# Elektronisch_schema_PCB.net
KiCad netlist of a schematic drawn in EasyEDA
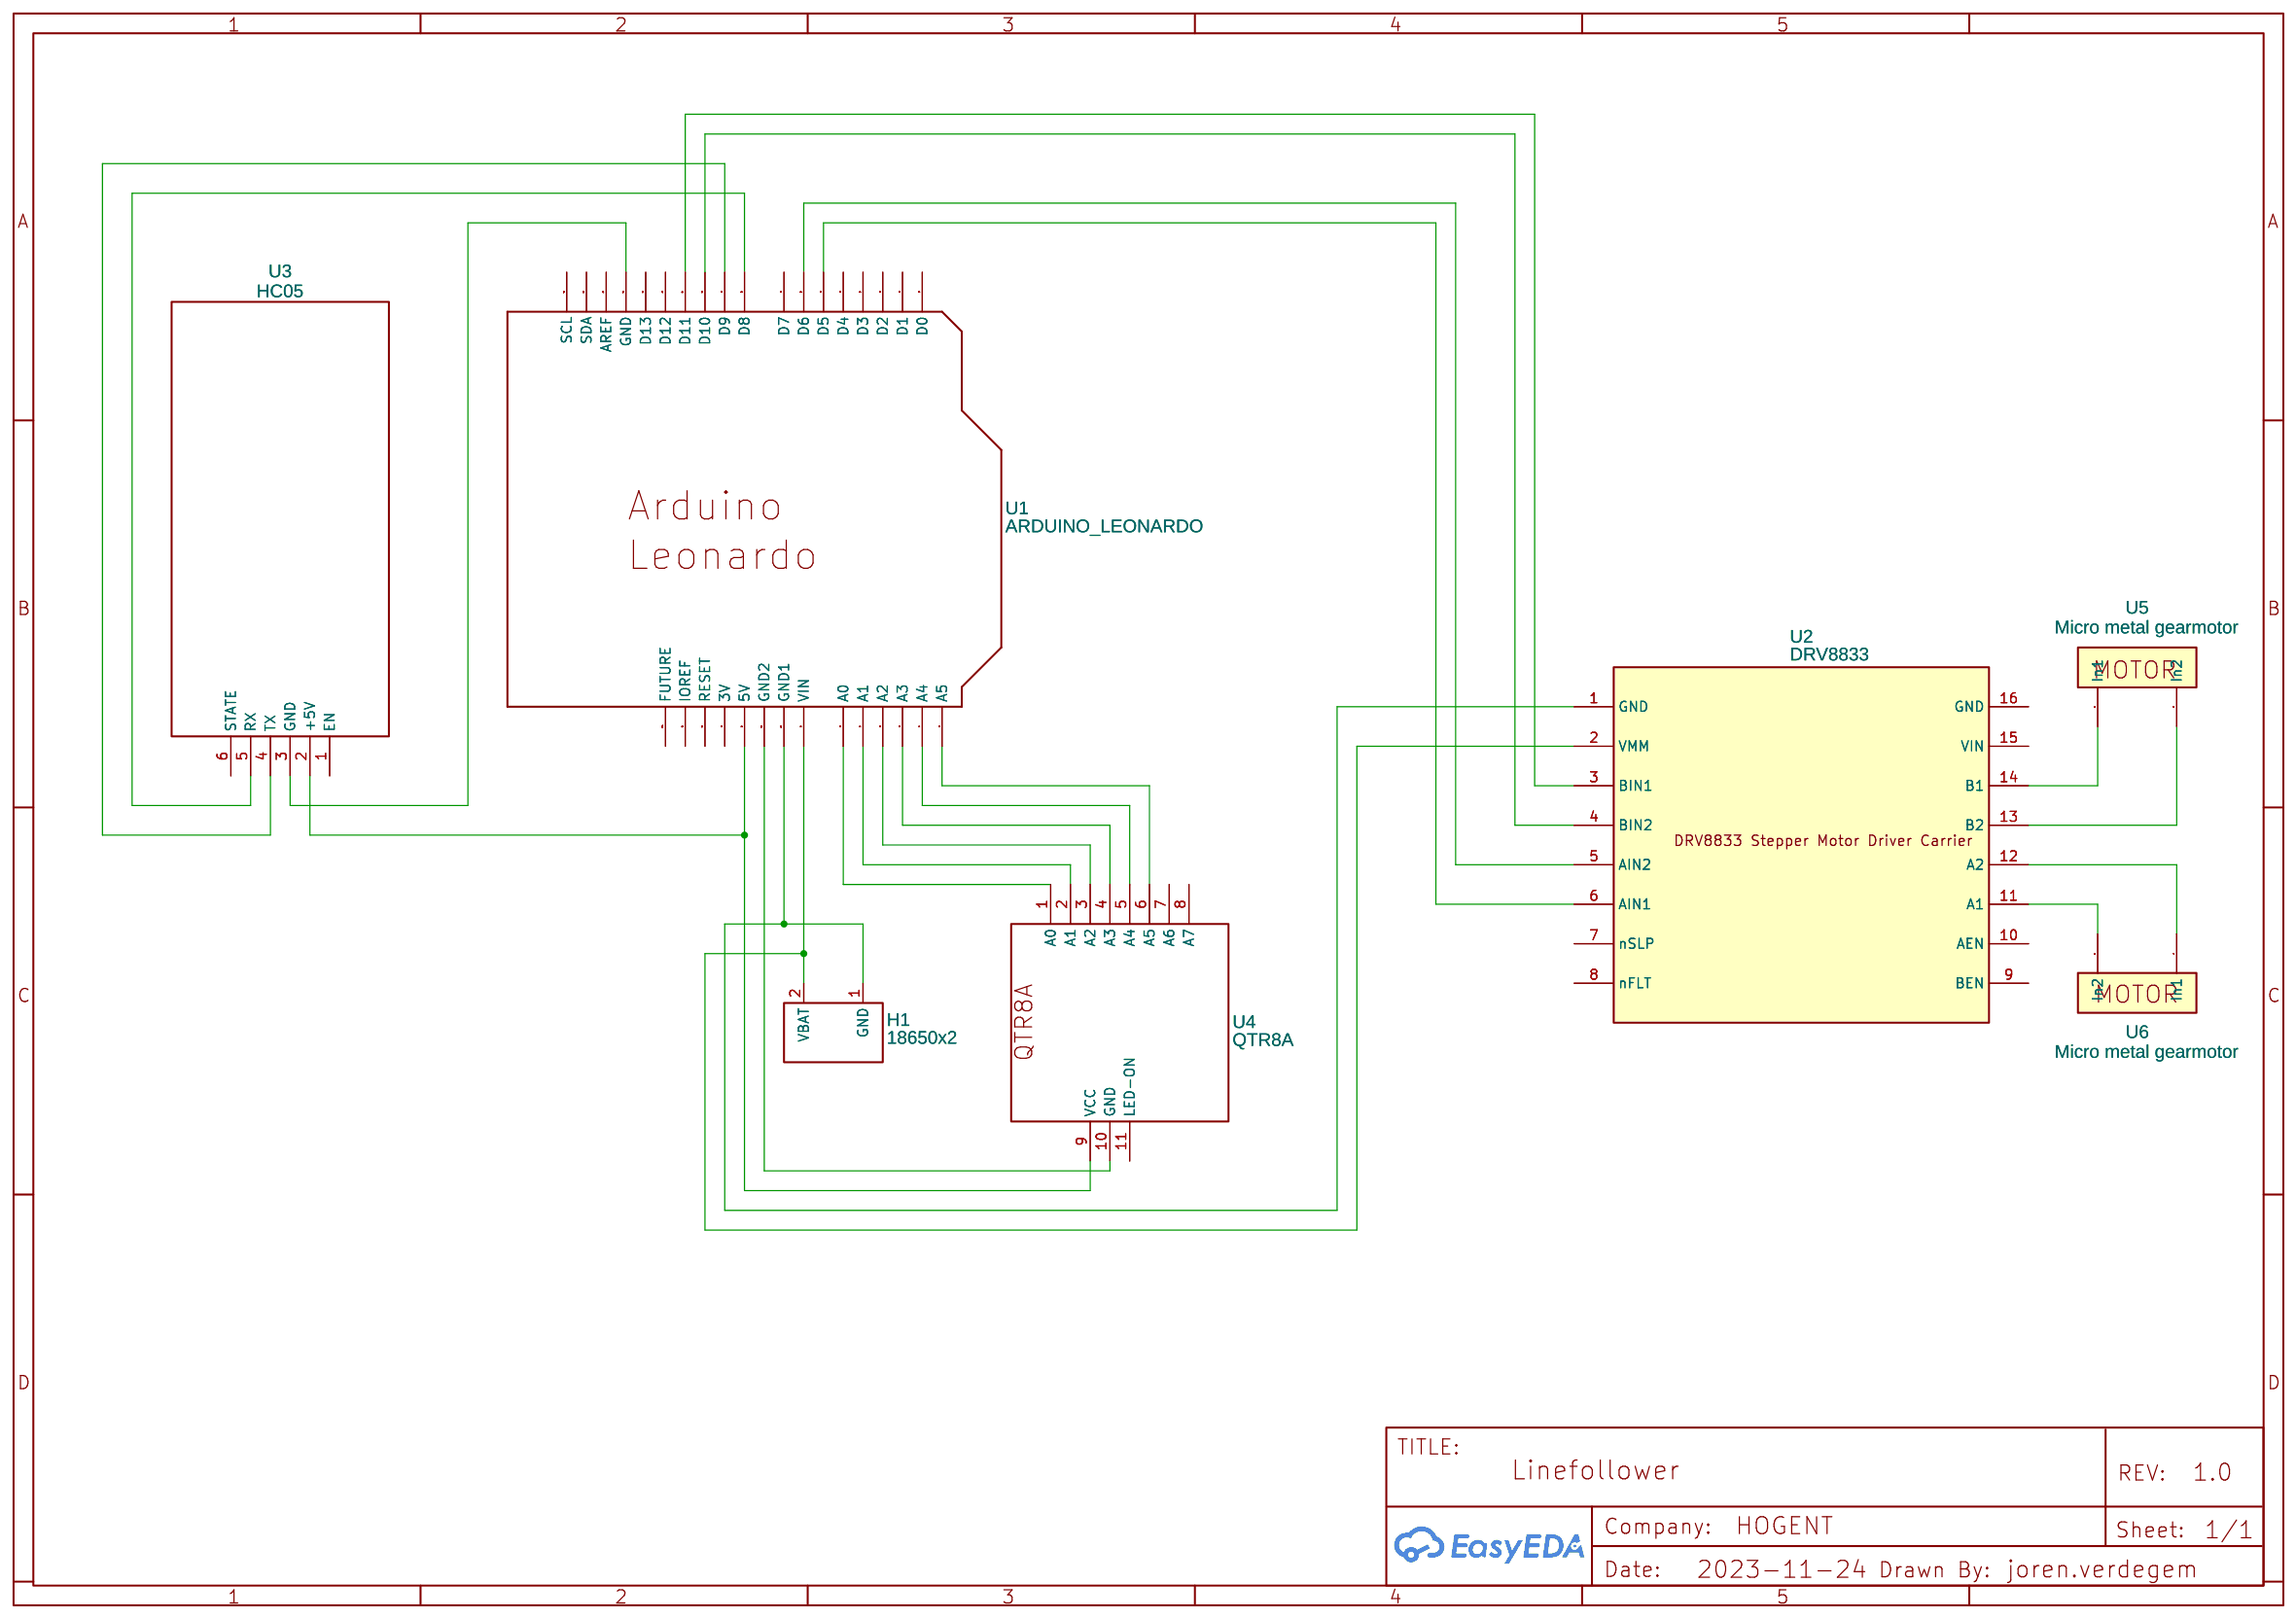
[diagram p0: schematic sheet]

(export (version "E")
  (design (tool "Eeschema 10.0.6"))
  (components
    (comp (ref "H1") (value "18650x2") (libsource (lib "") (part "18650x2")))
    (comp (ref "U1") (value "ARDUINO_LEONARDO") (libsource (lib "") (part "ARDUINO_LEONARDO")))
    (comp (ref "U2") (value "DRV8833") (libsource (lib "") (part "DRV8833 Stepper Motor Driver Carrier")))
    (comp (ref "U3") (value "HC05") (libsource (lib "") (part "HC05")))
    (comp (ref "U4")
      (value "QTR8A")
      (fields (field (name "Manufacturer") "POLOLU"))
      (libsource (lib "") (part "SCHLIB_QTR8A_2023-02-18"))
    )
    (comp (ref "U5")
      (value "Micro metal gearmotor")
      (fields (field (name "Manufacturer Part") "3062") (field (name "Manufacturer") "Pololu"))
      (libsource (lib "") (part "Micro metal gearmotor"))
    )
    (comp (ref "U6")
      (value "Micro metal gearmotor")
      (fields (field (name "Manufacturer Part") "3062") (field (name "Manufacturer") "Pololu"))
      (libsource (lib "") (part "Micro metal gearmotor_1"))
    )
  )
  (nets
    (net (code "1") (name "Net-(H1-GND)") (class "Default")
      (node (ref "H1") (pin "1") (pinfunction "GND_1") (pintype "unspecified"))
      (node (ref "U1") (pin "GND$3") (pinfunction "GND1_GND$3") (pintype "passive"))
      (node (ref "U2") (pin "1") (pinfunction "GND_1") (pintype "unspecified"))
    )
    (net (code "2") (name "Net-(H1-VBAT)") (class "Default")
      (node (ref "H1") (pin "2") (pinfunction "VBAT_2") (pintype "unspecified"))
      (node (ref "U1") (pin "VIN") (pinfunction "VIN_VIN") (pintype "passive"))
      (node (ref "U2") (pin "2") (pinfunction "VMM_2") (pintype "unspecified"))
    )
    (net (code "3") (name "Net-(U1-GND2)") (class "Default")
      (node (ref "U1") (pin "GND$2") (pinfunction "GND2_GND$2") (pintype "passive"))
      (node (ref "U4") (pin "10") (pinfunction "GND_10") (pintype "unspecified"))
    )
    (net (code "4") (name "Net-(U2-A1)") (class "Default")
      (node (ref "U2") (pin "11") (pinfunction "A1_11") (pintype "unspecified"))
      (node (ref "U6") (pin "2") (pinfunction "In2_2") (pintype "unspecified"))
    )
    (net (code "5") (name "Net-(U2-A2)") (class "Default")
      (node (ref "U2") (pin "12") (pinfunction "A2_12") (pintype "unspecified"))
      (node (ref "U6") (pin "1") (pinfunction "In1_1") (pintype "unspecified"))
    )
    (net (code "6") (name "Net-(U2-AIN1)") (class "Default")
      (node (ref "U1") (pin "D5") (pinfunction "D5_D5") (pintype "unspecified"))
      (node (ref "U2") (pin "6") (pinfunction "AIN1_6") (pintype "unspecified"))
    )
    (net (code "7") (name "Net-(U2-AIN2)") (class "Default")
      (node (ref "U1") (pin "D6") (pinfunction "D6_D6") (pintype "unspecified"))
      (node (ref "U2") (pin "5") (pinfunction "AIN2_5") (pintype "unspecified"))
    )
    (net (code "8") (name "Net-(U2-B1)") (class "Default")
      (node (ref "U2") (pin "14") (pinfunction "B1_14") (pintype "unspecified"))
      (node (ref "U5") (pin "1") (pinfunction "In1_1") (pintype "unspecified"))
    )
    (net (code "9") (name "Net-(U2-B2)") (class "Default")
      (node (ref "U2") (pin "13") (pinfunction "B2_13") (pintype "unspecified"))
      (node (ref "U5") (pin "2") (pinfunction "In2_2") (pintype "unspecified"))
    )
    (net (code "10") (name "Net-(U2-BIN1)") (class "Default")
      (node (ref "U1") (pin "D11") (pinfunction "D11_D11") (pintype "unspecified"))
      (node (ref "U2") (pin "3") (pinfunction "BIN1_3") (pintype "unspecified"))
    )
    (net (code "11") (name "Net-(U2-BIN2)") (class "Default")
      (node (ref "U1") (pin "D10") (pinfunction "D10_D10") (pintype "unspecified"))
      (node (ref "U2") (pin "4") (pinfunction "BIN2_4") (pintype "unspecified"))
    )
    (net (code "12") (name "Net-(U3-+5V)") (class "Default")
      (node (ref "U1") (pin "5V") (pinfunction "5V_5V") (pintype "passive"))
      (node (ref "U3") (pin "2") (pinfunction "+5V_2") (pintype "unspecified"))
      (node (ref "U4") (pin "9") (pinfunction "VCC_9") (pintype "unspecified"))
    )
    (net (code "13") (name "Net-(U3-GND)") (class "Default")
      (node (ref "U1") (pin "GND") (pinfunction "GND_GND") (pintype "passive"))
      (node (ref "U3") (pin "3") (pinfunction "GND_3") (pintype "unspecified"))
    )
    (net (code "14") (name "Net-(U3-RX)") (class "Default")
      (node (ref "U1") (pin "D8") (pinfunction "D8_D8") (pintype "unspecified"))
      (node (ref "U3") (pin "5") (pinfunction "RX_5") (pintype "unspecified"))
    )
    (net (code "15") (name "Net-(U3-TX)") (class "Default")
      (node (ref "U1") (pin "D9") (pinfunction "D9_D9") (pintype "unspecified"))
      (node (ref "U3") (pin "4") (pinfunction "TX_4") (pintype "unspecified"))
    )
    (net (code "16") (name "Net-(U4-A0)") (class "Default")
      (node (ref "U1") (pin "A0") (pinfunction "A0_A0") (pintype "unspecified"))
      (node (ref "U4") (pin "1") (pinfunction "A0_1") (pintype "unspecified"))
    )
    (net (code "17") (name "Net-(U4-A1)") (class "Default")
      (node (ref "U1") (pin "A1") (pinfunction "A1_A1") (pintype "unspecified"))
      (node (ref "U4") (pin "2") (pinfunction "A1_2") (pintype "unspecified"))
    )
    (net (code "18") (name "Net-(U4-A2)") (class "Default")
      (node (ref "U1") (pin "A2") (pinfunction "A2_A2") (pintype "unspecified"))
      (node (ref "U4") (pin "3") (pinfunction "A2_3") (pintype "unspecified"))
    )
    (net (code "19") (name "Net-(U4-A3)") (class "Default")
      (node (ref "U1") (pin "A3") (pinfunction "A3_A3") (pintype "unspecified"))
      (node (ref "U4") (pin "4") (pinfunction "A3_4") (pintype "unspecified"))
    )
    (net (code "20") (name "Net-(U4-A4)") (class "Default")
      (node (ref "U1") (pin "A4") (pinfunction "A4_A4") (pintype "unspecified"))
      (node (ref "U4") (pin "5") (pinfunction "A4_5") (pintype "unspecified"))
    )
    (net (code "21") (name "Net-(U4-A5)") (class "Default")
      (node (ref "U1") (pin "A5") (pinfunction "A5_A5") (pintype "unspecified"))
      (node (ref "U4") (pin "6") (pinfunction "A5_6") (pintype "unspecified"))
    )
    (net (code "22") (name "unconnected-(U1-FUTURE-PadRESERVED)") (class "Default")
      (node (ref "U1") (pin "RESERVED") (pinfunction "FUTURE_RESERVED") (pintype "unspecified"))
    )
    (net (code "23") (name "unconnected-(U1-Pad3V)") (class "Default")
      (node (ref "U1") (pin "3V") (pinfunction "3V_3V") (pintype "passive"))
    )
    (net (code "24") (name "unconnected-(U1-PadAREF)") (class "Default")
      (node (ref "U1") (pin "AREF") (pinfunction "AREF_AREF") (pintype "unspecified"))
    )
    (net (code "25") (name "unconnected-(U1-PadD0)") (class "Default")
      (node (ref "U1") (pin "D0") (pinfunction "D0_D0") (pintype "unspecified"))
    )
    (net (code "26") (name "unconnected-(U1-PadD1)") (class "Default")
      (node (ref "U1") (pin "D1") (pinfunction "D1_D1") (pintype "unspecified"))
    )
    (net (code "27") (name "unconnected-(U1-PadD2)") (class "Default")
      (node (ref "U1") (pin "D2") (pinfunction "D2_D2") (pintype "unspecified"))
    )
    (net (code "28") (name "unconnected-(U1-PadD3)") (class "Default")
      (node (ref "U1") (pin "D3") (pinfunction "D3_D3") (pintype "unspecified"))
    )
    (net (code "29") (name "unconnected-(U1-PadD4)") (class "Default")
      (node (ref "U1") (pin "D4") (pinfunction "D4_D4") (pintype "unspecified"))
    )
    (net (code "30") (name "unconnected-(U1-PadD7)") (class "Default")
      (node (ref "U1") (pin "D7") (pinfunction "D7_D7") (pintype "unspecified"))
    )
    (net (code "31") (name "unconnected-(U1-PadD12)") (class "Default")
      (node (ref "U1") (pin "D12") (pinfunction "D12_D12") (pintype "unspecified"))
    )
    (net (code "32") (name "unconnected-(U1-PadD13)") (class "Default")
      (node (ref "U1") (pin "D13") (pinfunction "D13_D13") (pintype "unspecified"))
    )
    (net (code "33") (name "unconnected-(U1-PadIOREF)") (class "Default")
      (node (ref "U1") (pin "IOREF") (pinfunction "IOREF_IOREF") (pintype "unspecified"))
    )
    (net (code "34") (name "unconnected-(U1-PadRESET)") (class "Default")
      (node (ref "U1") (pin "RESET") (pinfunction "RESET_RESET") (pintype "unspecified"))
    )
    (net (code "35") (name "unconnected-(U1-PadSCL)") (class "Default")
      (node (ref "U1") (pin "SCL") (pinfunction "SCL_SCL") (pintype "unspecified"))
    )
    (net (code "36") (name "unconnected-(U1-PadSDA)") (class "Default")
      (node (ref "U1") (pin "SDA") (pinfunction "SDA_SDA") (pintype "unspecified"))
    )
    (net (code "37") (name "unconnected-(U2-AEN-Pad10)") (class "Default")
      (node (ref "U2") (pin "10") (pinfunction "AEN_10") (pintype "unspecified"))
    )
    (net (code "38") (name "unconnected-(U2-BEN-Pad9)") (class "Default")
      (node (ref "U2") (pin "9") (pinfunction "BEN_9") (pintype "unspecified"))
    )
    (net (code "39") (name "unconnected-(U2-GND-Pad16)") (class "Default")
      (node (ref "U2") (pin "16") (pinfunction "GND_16") (pintype "unspecified"))
    )
    (net (code "40") (name "unconnected-(U2-VIN-Pad15)") (class "Default")
      (node (ref "U2") (pin "15") (pinfunction "VIN_15") (pintype "unspecified"))
    )
    (net (code "41") (name "unconnected-(U2-nFLT-Pad8)") (class "Default")
      (node (ref "U2") (pin "8") (pinfunction "nFLT_8") (pintype "unspecified"))
    )
    (net (code "42") (name "unconnected-(U2-nSLP-Pad7)") (class "Default")
      (node (ref "U2") (pin "7") (pinfunction "nSLP_7") (pintype "unspecified"))
    )
    (net (code "43") (name "unconnected-(U3-EN-Pad1)") (class "Default")
      (node (ref "U3") (pin "1") (pinfunction "EN_1") (pintype "unspecified"))
    )
    (net (code "44") (name "unconnected-(U3-STATE-Pad6)") (class "Default")
      (node (ref "U3") (pin "6") (pinfunction "STATE_6") (pintype "unspecified"))
    )
    (net (code "45") (name "unconnected-(U4-A6-Pad7)") (class "Default")
      (node (ref "U4") (pin "7") (pinfunction "A6_7") (pintype "unspecified"))
    )
    (net (code "46") (name "unconnected-(U4-A7-Pad8)") (class "Default")
      (node (ref "U4") (pin "8") (pinfunction "A7_8") (pintype "unspecified"))
    )
    (net (code "47") (name "unconnected-(U4-LED-ON-Pad11)") (class "Default")
      (node (ref "U4") (pin "11") (pinfunction "LED-ON_11") (pintype "unspecified"))
    )
  )
)
